# LED_Display_4dig.net
KiCad netlist of a schematic drawn in EAGLE
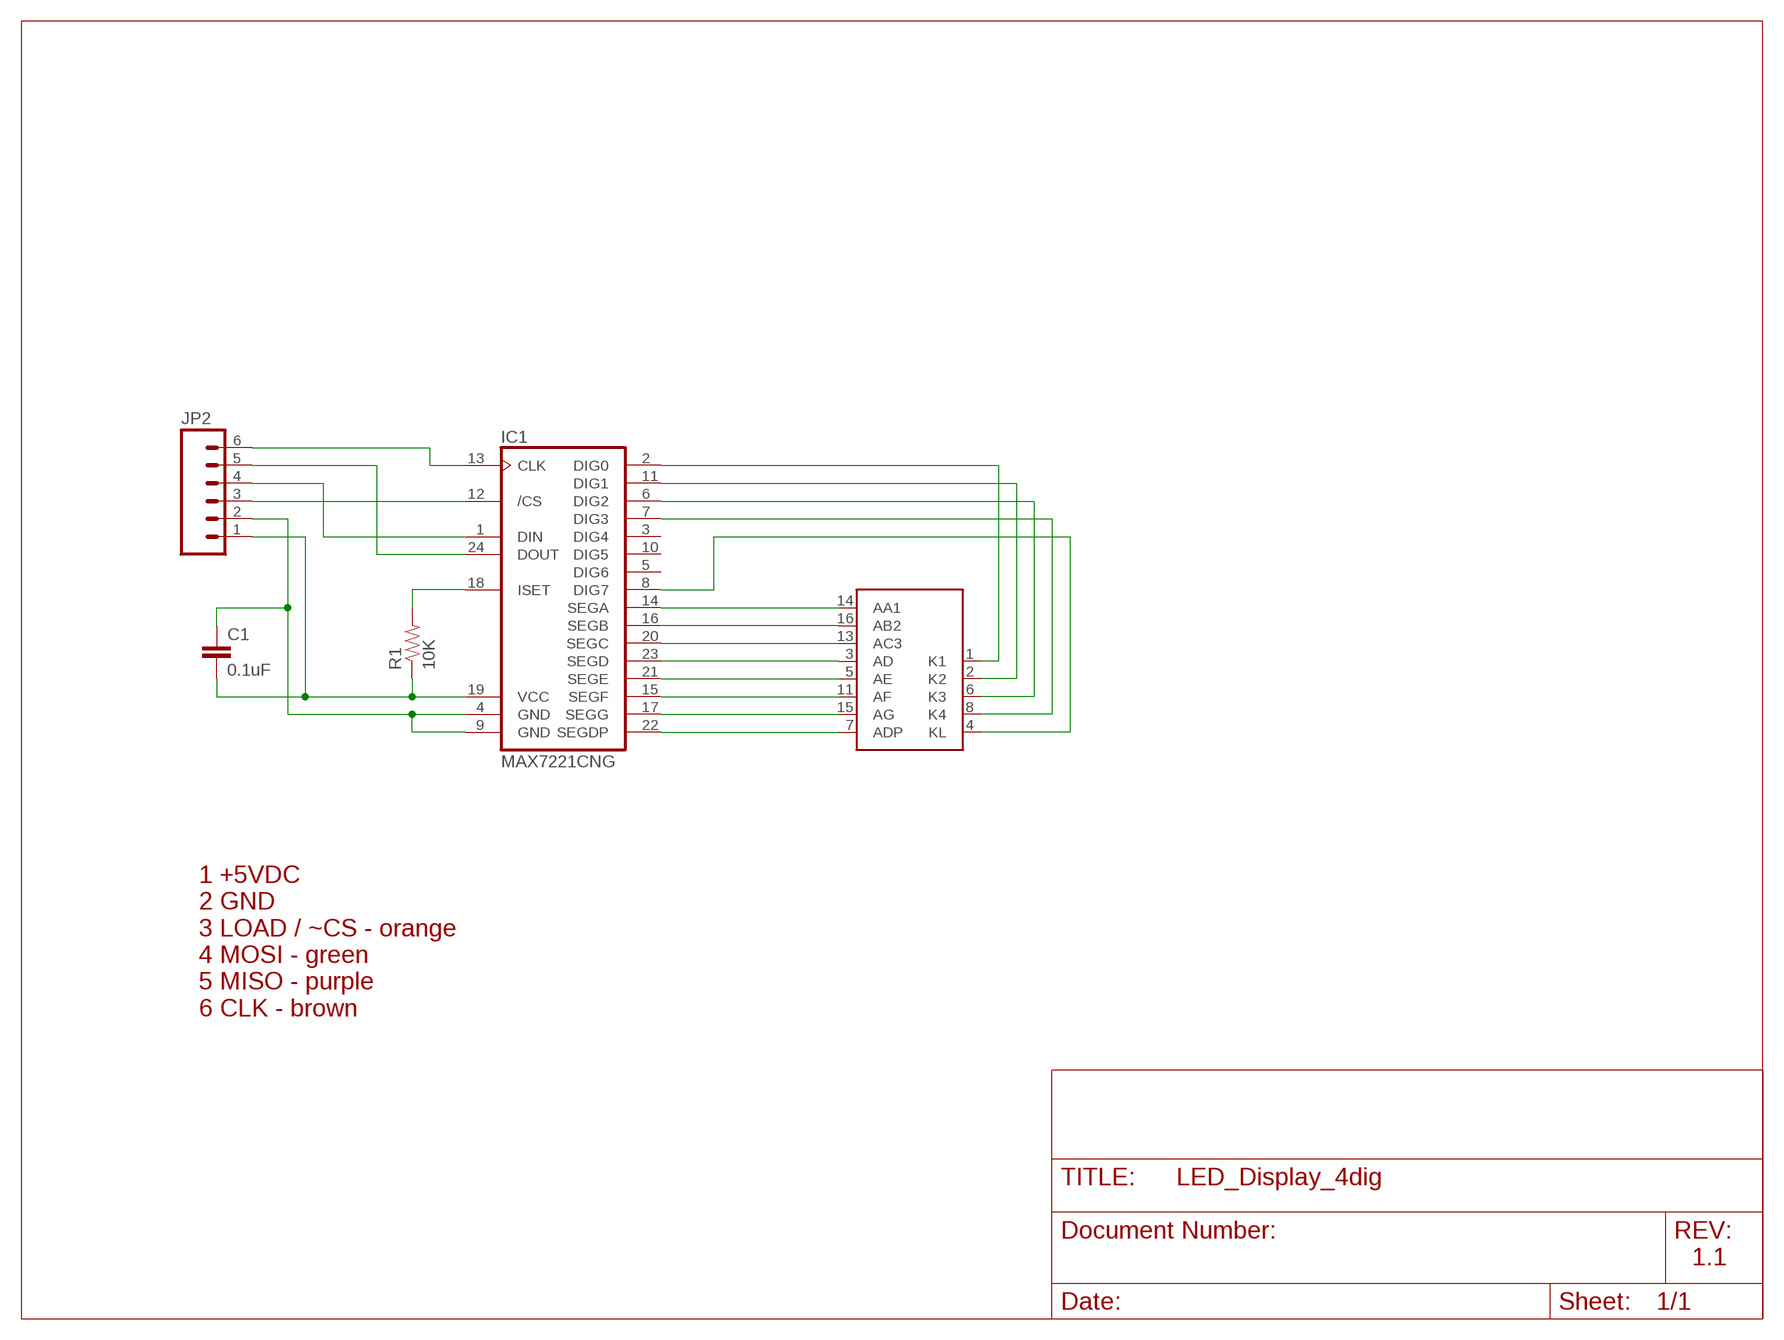
[diagram p0: schematic, sheet 1]

(export (version "E")
  (design (tool "Eeschema 10.0.6"))
  (components
    (comp (ref "C1")
      (value "0.1uF")
      (footprint "eagle-import:CAP-PTH-SMALL")
      (libsource (lib "eagle-import") (part "CAPPTH"))
    )
    (comp (ref "IC1")
      (value "MAX7221CNG")
      (footprint "eagle-import:DIL24-3")
      (libsource (lib "eagle-import") (part "MAX7221NGC"))
    )
    (comp (ref "JP2")
      (value "M06LOCK_LONGPADS")
      (footprint "eagle-import:1X06_LOCK_LONGPADS")
      (libsource (lib "eagle-import") (part "M06LOCK_LONGPADS"))
    )
    (comp (ref "R1")
      (value "10K")
      (footprint "eagle-import:AXIAL-0.4")
      (libsource (lib "eagle-import") (part "RESISTORPTH-1/4W"))
    )
    (comp (ref "U$1")
      (value "LTC-4027JRLTC-4027JR")
      (footprint "eagle-import:LTC-4727JR")
      (libsource (lib "eagle-import") (part "LTC-4027JRLTC-4027JR"))
    )
  )
  (nets
    (net (code "1") (name "Net-(C1-Pad1)") (class "Default")
      (node (ref "C1") (pin "1") (pinfunction "1_1") (pintype "passive"))
      (node (ref "IC1") (pin "4") (pinfunction "GND_4") (pintype "power_in"))
      (node (ref "IC1") (pin "9") (pinfunction "GND_9") (pintype "power_in"))
      (node (ref "JP2") (pin "2") (pinfunction "2_2") (pintype "passive"))
    )
    (net (code "2") (name "Net-(IC1-CLK)") (class "Default")
      (node (ref "IC1") (pin "13") (pinfunction "CLK_13") (pintype "input"))
      (node (ref "JP2") (pin "6") (pinfunction "6_6") (pintype "passive"))
    )
    (net (code "3") (name "Net-(IC1-DIG0)") (class "Default")
      (node (ref "IC1") (pin "2") (pinfunction "DIG0_2") (pintype "open_collector"))
      (node (ref "U$1") (pin "1") (pinfunction "K1_1") (pintype "bidirectional"))
    )
    (net (code "4") (name "Net-(IC1-DIG1)") (class "Default")
      (node (ref "IC1") (pin "11") (pinfunction "DIG1_11") (pintype "open_collector"))
      (node (ref "U$1") (pin "2") (pinfunction "K2_2") (pintype "bidirectional"))
    )
    (net (code "5") (name "Net-(IC1-DIG2)") (class "Default")
      (node (ref "IC1") (pin "6") (pinfunction "DIG2_6") (pintype "open_collector"))
      (node (ref "U$1") (pin "6") (pinfunction "K3_6") (pintype "bidirectional"))
    )
    (net (code "6") (name "Net-(IC1-DIG3)") (class "Default")
      (node (ref "IC1") (pin "7") (pinfunction "DIG3_7") (pintype "open_collector"))
      (node (ref "U$1") (pin "8") (pinfunction "K4_8") (pintype "bidirectional"))
    )
    (net (code "7") (name "Net-(IC1-DIG7)") (class "Default")
      (node (ref "IC1") (pin "8") (pinfunction "DIG7_8") (pintype "open_collector"))
      (node (ref "U$1") (pin "4") (pinfunction "KL_4") (pintype "bidirectional"))
    )
    (net (code "8") (name "Net-(IC1-DIN)") (class "Default")
      (node (ref "IC1") (pin "1") (pinfunction "DIN_1") (pintype "input"))
      (node (ref "JP2") (pin "4") (pinfunction "4_4") (pintype "passive"))
    )
    (net (code "9") (name "Net-(IC1-DOUT)") (class "Default")
      (node (ref "IC1") (pin "24") (pinfunction "DOUT_24") (pintype "output"))
      (node (ref "JP2") (pin "5") (pinfunction "5_5") (pintype "passive"))
    )
    (net (code "10") (name "Net-(IC1-ISET)") (class "Default")
      (node (ref "IC1") (pin "18") (pinfunction "ISET_18") (pintype "input"))
      (node (ref "R1") (pin "P$2") (pinfunction "2_P$2") (pintype "passive"))
    )
    (net (code "11") (name "Net-(IC1-SEGA)") (class "Default")
      (node (ref "IC1") (pin "14") (pinfunction "SEGA_14") (pintype "output"))
      (node (ref "U$1") (pin "14") (pinfunction "AA1_14") (pintype "bidirectional"))
    )
    (net (code "12") (name "Net-(IC1-SEGB)") (class "Default")
      (node (ref "IC1") (pin "16") (pinfunction "SEGB_16") (pintype "output"))
      (node (ref "U$1") (pin "16") (pinfunction "AB2_16") (pintype "bidirectional"))
    )
    (net (code "13") (name "Net-(IC1-SEGC)") (class "Default")
      (node (ref "IC1") (pin "20") (pinfunction "SEGC_20") (pintype "output"))
      (node (ref "U$1") (pin "13") (pinfunction "AC3_13") (pintype "bidirectional"))
    )
    (net (code "14") (name "Net-(IC1-SEGD)") (class "Default")
      (node (ref "IC1") (pin "23") (pinfunction "SEGD_23") (pintype "output"))
      (node (ref "U$1") (pin "3") (pinfunction "AD_3") (pintype "bidirectional"))
    )
    (net (code "15") (name "Net-(IC1-SEGDP)") (class "Default")
      (node (ref "IC1") (pin "22") (pinfunction "SEGDP_22") (pintype "output"))
      (node (ref "U$1") (pin "7") (pinfunction "ADP_7") (pintype "bidirectional"))
    )
    (net (code "16") (name "Net-(IC1-SEGE)") (class "Default")
      (node (ref "IC1") (pin "21") (pinfunction "SEGE_21") (pintype "output"))
      (node (ref "U$1") (pin "5") (pinfunction "AE_5") (pintype "bidirectional"))
    )
    (net (code "17") (name "Net-(IC1-SEGF)") (class "Default")
      (node (ref "IC1") (pin "15") (pinfunction "SEGF_15") (pintype "output"))
      (node (ref "U$1") (pin "11") (pinfunction "AF_11") (pintype "bidirectional"))
    )
    (net (code "18") (name "Net-(IC1-SEGG)") (class "Default")
      (node (ref "IC1") (pin "17") (pinfunction "SEGG_17") (pintype "output"))
      (node (ref "U$1") (pin "15") (pinfunction "AG_15") (pintype "bidirectional"))
    )
    (net (code "19") (name "Net-(IC1-VCC)") (class "Default")
      (node (ref "C1") (pin "2") (pinfunction "2_2") (pintype "passive"))
      (node (ref "IC1") (pin "19") (pinfunction "VCC_19") (pintype "power_in"))
      (node (ref "JP2") (pin "1") (pinfunction "1_1") (pintype "passive"))
      (node (ref "R1") (pin "P$1") (pinfunction "1_P$1") (pintype "passive"))
    )
    (net (code "20") (name "Net-(IC1-{slash}CS)") (class "Default")
      (node (ref "IC1") (pin "12") (pinfunction "/CS_12") (pintype "input"))
      (node (ref "JP2") (pin "3") (pinfunction "3_3") (pintype "passive"))
    )
    (net (code "21") (name "unconnected-(IC1-DIG4-Pad3)") (class "Default")
      (node (ref "IC1") (pin "3") (pinfunction "DIG4_3") (pintype "open_collector"))
    )
    (net (code "22") (name "unconnected-(IC1-DIG5-Pad10)") (class "Default")
      (node (ref "IC1") (pin "10") (pinfunction "DIG5_10") (pintype "open_collector"))
    )
    (net (code "23") (name "unconnected-(IC1-DIG6-Pad5)") (class "Default")
      (node (ref "IC1") (pin "5") (pinfunction "DIG6_5") (pintype "open_collector"))
    )
  )
)
